# e202-wickervar.net
KiCad netlist of a schematic drawn in EAGLE
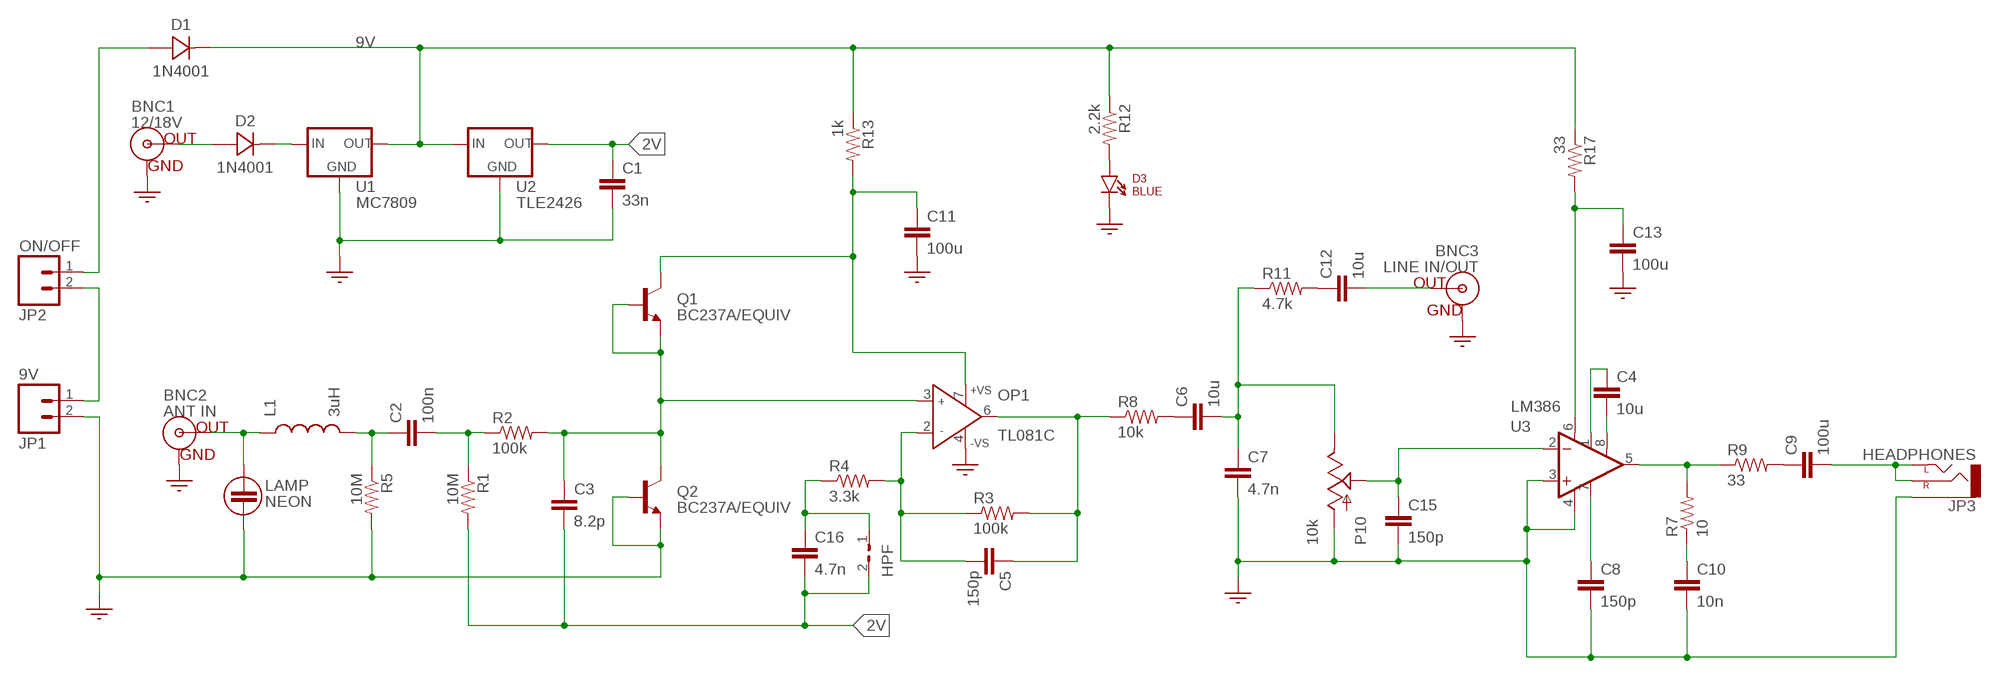
[diagram p0: schematic, sheet 1]

(export (version "E")
  (design (tool "Eeschema 10.0.6"))
  (components
    (comp (ref "BNC1")
      (value "12/18V")
      (footprint "eagle-import:BNC")
      (libsource (lib "eagle-import") (part "BNCPTH"))
    )
    (comp (ref "BNC2")
      (value "ANT IN")
      (footprint "eagle-import:BNC")
      (libsource (lib "eagle-import") (part "BNCPTH"))
    )
    (comp (ref "BNC3")
      (value "LINE IN/OUT")
      (footprint "eagle-import:BNC")
      (libsource (lib "eagle-import") (part "BNCPTH"))
    )
    (comp (ref "C1")
      (value "33n")
      (footprint "eagle-import:CAP-PTH-SMALL-KIT")
      (libsource (lib "eagle-import") (part "CAPKIT"))
    )
    (comp (ref "C2")
      (value "100n")
      (footprint "eagle-import:CAP-PTH-SMALL-KIT")
      (libsource (lib "eagle-import") (part "CAPKIT"))
    )
    (comp (ref "C3")
      (value "8.2p")
      (footprint "eagle-import:CAP-PTH-SMALL-KIT")
      (libsource (lib "eagle-import") (part "CAPKIT"))
    )
    (comp (ref "C4")
      (value "10u")
      (footprint "eagle-import:CAP-PTH-5MM")
      (libsource (lib "eagle-import") (part "SparkFun-Passives_CAPPTH1"))
    )
    (comp (ref "C5")
      (value "150p")
      (footprint "eagle-import:CAP-PTH-SMALL-KIT")
      (libsource (lib "eagle-import") (part "CAPKIT"))
    )
    (comp (ref "C6")
      (value "10u")
      (footprint "eagle-import:CAP-PTH-5MM")
      (libsource (lib "eagle-import") (part "SparkFun-Passives_CAPPTH1"))
    )
    (comp (ref "C7")
      (value "4.7n")
      (footprint "eagle-import:CAP-PTH-5MM")
      (libsource (lib "eagle-import") (part "SparkFun-Passives_CAPPTH1"))
    )
    (comp (ref "C8")
      (value "150p")
      (footprint "eagle-import:CAP-PTH-SMALL-KIT")
      (libsource (lib "eagle-import") (part "CAPKIT"))
    )
    (comp (ref "C9")
      (value "100u")
      (footprint "eagle-import:CAP-PTH-5MM")
      (libsource (lib "eagle-import") (part "SparkFun-Passives_CAPPTH1"))
    )
    (comp (ref "C10")
      (value "10n")
      (footprint "eagle-import:CAP-PTH-SMALL-KIT")
      (libsource (lib "eagle-import") (part "CAPKIT"))
    )
    (comp (ref "C11")
      (value "100u")
      (footprint "eagle-import:CAP-PTH-5MM")
      (libsource (lib "eagle-import") (part "SparkFun-Passives_CAPPTH1"))
    )
    (comp (ref "C12")
      (value "10u")
      (footprint "eagle-import:CAP-PTH-5MM")
      (libsource (lib "eagle-import") (part "SparkFun-Passives_CAPPTH1"))
    )
    (comp (ref "C13")
      (value "100u")
      (footprint "eagle-import:CAP-PTH-5MM")
      (libsource (lib "eagle-import") (part "SparkFun-Passives_CAPPTH1"))
    )
    (comp (ref "C15")
      (value "150p")
      (footprint "eagle-import:CAP-PTH-SMALL-KIT")
      (libsource (lib "eagle-import") (part "CAPKIT"))
    )
    (comp (ref "C16")
      (value "4.7n")
      (footprint "eagle-import:CAP-PTH-SMALL-KIT")
      (libsource (lib "eagle-import") (part "CAPKIT"))
    )
    (comp (ref "D1")
      (value "1N4001")
      (footprint "eagle-import:SMC")
      (libsource (lib "eagle-import") (part "S5BC-13"))
    )
    (comp (ref "D2")
      (value "1N4001")
      (footprint "eagle-import:SMC")
      (libsource (lib "eagle-import") (part "S5BC-13"))
    )
    (comp (ref "D3")
      (value "BLUE")
      (footprint "eagle-import:LTE-302")
      (libsource (lib "eagle-import") (part "LTE-302"))
    )
    (comp (ref "HPF")
      (value "HPF")
      (footprint "eagle-import:1X02_LOCK")
      (libsource (lib "eagle-import") (part "JUMPER-2PTH_LOCK"))
    )
    (comp (ref "JP1")
      (value "9V")
      (footprint "eagle-import:1X02_LOCK")
      (libsource (lib "eagle-import") (part "M02LOCK"))
    )
    (comp (ref "JP2")
      (value "ON/OFF")
      (footprint "eagle-import:1X02_LOCK")
      (libsource (lib "eagle-import") (part "M02LOCK"))
    )
    (comp (ref "JP3")
      (value "HEADPHONES")
      (footprint "eagle-import:STEREOJACK2.5MM_STEREOJACK2.5MM")
      (libsource (lib "eagle-import") (part "AUDIO-JACK2.5MM"))
    )
    (comp (ref "L1")
      (value "3uH")
      (footprint "eagle-import:AXIAL-0.6")
      (libsource (lib "eagle-import") (part "INDUCTORAXIAL-0.6"))
    )
    (comp (ref "LAMP")
      (value "NEON")
      (footprint "eagle-import:ESK337M050AH4AA")
      (libsource (lib "eagle-import") (part "NEONLAMP"))
    )
    (comp (ref "OP1")
      (value "TL081C")
      (footprint "eagle-import:LFCSP8")
      (libsource (lib "eagle-import") (part "AD8597CP"))
    )
    (comp (ref "P10")
      (value "10k")
      (footprint "eagle-import:ALPS_POT")
      (libsource (lib "eagle-import") (part "POT"))
    )
    (comp (ref "Q1")
      (value "BC237A/EQUIV")
      (footprint "eagle-import:TO-92-AMMO")
      (libsource (lib "eagle-import") (part "TRANSISTOR_NPNBC547"))
    )
    (comp (ref "Q2")
      (value "BC237A/EQUIV")
      (footprint "eagle-import:TO-92-AMMO")
      (libsource (lib "eagle-import") (part "TRANSISTOR_NPNBC547"))
    )
    (comp (ref "R1")
      (value "10M")
      (footprint "eagle-import:AXIAL-0.3EZ")
      (libsource (lib "eagle-import") (part "RESISTOREZ"))
    )
    (comp (ref "R2")
      (value "100k")
      (footprint "eagle-import:AXIAL-0.3EZ")
      (libsource (lib "eagle-import") (part "RESISTOREZ"))
    )
    (comp (ref "R3")
      (value "100k")
      (footprint "eagle-import:AXIAL-0.3EZ")
      (libsource (lib "eagle-import") (part "RESISTOREZ"))
    )
    (comp (ref "R4")
      (value "3.3k")
      (footprint "eagle-import:AXIAL-0.3EZ")
      (libsource (lib "eagle-import") (part "RESISTOREZ"))
    )
    (comp (ref "R5")
      (value "10M")
      (footprint "eagle-import:AXIAL-0.3EZ")
      (libsource (lib "eagle-import") (part "RESISTOREZ"))
    )
    (comp (ref "R7")
      (value "10")
      (footprint "eagle-import:AXIAL-0.3EZ")
      (libsource (lib "eagle-import") (part "RESISTOREZ"))
    )
    (comp (ref "R8")
      (value "10k")
      (footprint "eagle-import:AXIAL-0.3EZ")
      (libsource (lib "eagle-import") (part "RESISTOREZ"))
    )
    (comp (ref "R9")
      (value "33")
      (footprint "eagle-import:AXIAL-0.3EZ")
      (libsource (lib "eagle-import") (part "RESISTOREZ"))
    )
    (comp (ref "R11")
      (value "4.7k")
      (footprint "eagle-import:AXIAL-0.3EZ")
      (libsource (lib "eagle-import") (part "RESISTOREZ"))
    )
    (comp (ref "R12")
      (value "2.2k")
      (footprint "eagle-import:AXIAL-0.3EZ")
      (libsource (lib "eagle-import") (part "RESISTOREZ"))
    )
    (comp (ref "R13")
      (value "1k")
      (footprint "eagle-import:AXIAL-0.3EZ")
      (libsource (lib "eagle-import") (part "RESISTOREZ"))
    )
    (comp (ref "R17")
      (value "33")
      (footprint "eagle-import:AXIAL-0.3EZ")
      (libsource (lib "eagle-import") (part "RESISTOREZ"))
    )
    (comp (ref "U1")
      (value "MC7809")
      (footprint "eagle-import:78XXL")
      (libsource (lib "eagle-import") (part "V_REG_LD1117VXX"))
    )
    (comp (ref "U2")
      (value "TLE2426")
      (footprint "eagle-import:78XXL")
      (libsource (lib "eagle-import") (part "V_REG_LD1117VXX"))
    )
    (comp (ref "U3")
      (value "LM386")
      (footprint "eagle-import:DIP08")
      (libsource (lib "eagle-import") (part "LM386"))
    )
  )
  (nets
    (net (code "1") (name "/9V") (class "Default")
      (node (ref "D1") (pin "C") (pinfunction "CATHODE_C") (pintype "passive"))
      (node (ref "R12") (pin "P$1") (pinfunction "1_P$1") (pintype "passive"))
      (node (ref "R13") (pin "P$1") (pinfunction "1_P$1") (pintype "passive"))
      (node (ref "R17") (pin "P$1") (pinfunction "1_P$1") (pintype "passive"))
      (node (ref "U1") (pin "GND") (pinfunction "OUT_GND") (pintype "output"))
      (node (ref "U2") (pin "OUT") (pinfunction "IN_OUT") (pintype "input"))
    )
    (net (code "2") (name "2V") (class "Default")
      (node (ref "C1") (pin "1") (pinfunction "1_1") (pintype "passive"))
      (node (ref "C16") (pin "2") (pinfunction "2_2") (pintype "passive"))
      (node (ref "C3") (pin "2") (pinfunction "2_2") (pintype "passive"))
      (node (ref "HPF") (pin "2") (pinfunction "2_2") (pintype "passive"))
      (node (ref "R1") (pin "P$2") (pinfunction "2_P$2") (pintype "passive"))
      (node (ref "U2") (pin "GND") (pinfunction "OUT_GND") (pintype "output"))
    )
    (net (code "3") (name "GND") (class "Default")
      (node (ref "BNC1") (pin "GND") (pinfunction "GND_GND") (pintype "bidirectional"))
      (node (ref "BNC2") (pin "GND") (pinfunction "GND_GND") (pintype "bidirectional"))
      (node (ref "BNC3") (pin "GND") (pinfunction "GND_GND") (pintype "bidirectional"))
      (node (ref "C1") (pin "2") (pinfunction "2_2") (pintype "passive"))
      (node (ref "C10") (pin "2") (pinfunction "2_2") (pintype "passive"))
      (node (ref "C11") (pin "2") (pinfunction "2_2") (pintype "passive"))
      (node (ref "C13") (pin "2") (pinfunction "2_2") (pintype "passive"))
      (node (ref "C15") (pin "2") (pinfunction "2_2") (pintype "passive"))
      (node (ref "C7") (pin "2") (pinfunction "2_2") (pintype "passive"))
      (node (ref "C8") (pin "2") (pinfunction "2_2") (pintype "passive"))
      (node (ref "D3") (pin "C") (pinfunction "C_C") (pintype "bidirectional"))
      (node (ref "JP1") (pin "2") (pinfunction "2_2") (pintype "passive"))
      (node (ref "JP3") (pin "RING1") (pinfunction "SLEEVE_RING1") (pintype "bidirectional"))
      (node (ref "LAMP") (pin "C") (pinfunction "2_C") (pintype "passive"))
      (node (ref "OP1") (pin "4") (pinfunction "-VS_4") (pintype "input"))
      (node (ref "P10") (pin "P$3") (pinfunction "A_P$3") (pintype "passive"))
      (node (ref "Q2") (pin "2") (pinfunction "B_2") (pintype "passive"))
      (node (ref "Q2") (pin "3") (pinfunction "E_3") (pintype "passive"))
      (node (ref "R5") (pin "P$2") (pinfunction "2_P$2") (pintype "passive"))
      (node (ref "U1") (pin "IN") (pinfunction "GND_IN") (pintype "input"))
      (node (ref "U2") (pin "IN") (pinfunction "GND_IN") (pintype "input"))
      (node (ref "U3") (pin "3") (pinfunction "+IN_3") (pintype "input"))
      (node (ref "U3") (pin "4") (pinfunction "V-_4") (pintype "power_in"))
    )
    (net (code "4") (name "Net-(BNC1-OUT)") (class "Default")
      (node (ref "BNC1") (pin "S") (pinfunction "OUT_S") (pintype "bidirectional"))
      (node (ref "D2") (pin "A") (pinfunction "ANODE_A") (pintype "passive"))
    )
    (net (code "5") (name "Net-(BNC2-OUT)") (class "Default")
      (node (ref "BNC2") (pin "S") (pinfunction "OUT_S") (pintype "bidirectional"))
      (node (ref "L1") (pin "P$1") (pinfunction "1_P$1") (pintype "passive"))
      (node (ref "LAMP") (pin "A") (pinfunction "1_A") (pintype "passive"))
    )
    (net (code "6") (name "Net-(BNC3-OUT)") (class "Default")
      (node (ref "BNC3") (pin "S") (pinfunction "OUT_S") (pintype "bidirectional"))
      (node (ref "C12") (pin "2") (pinfunction "2_2") (pintype "passive"))
    )
    (net (code "7") (name "Net-(C4-Pad1)") (class "Default")
      (node (ref "C4") (pin "1") (pinfunction "1_1") (pintype "passive"))
      (node (ref "U3") (pin "1") (pinfunction "GAIN_1") (pintype "bidirectional"))
    )
    (net (code "8") (name "Net-(C4-Pad2)") (class "Default")
      (node (ref "C4") (pin "2") (pinfunction "2_2") (pintype "passive"))
      (node (ref "U3") (pin "8") (pinfunction "GAIN_8") (pintype "bidirectional"))
    )
    (net (code "9") (name "Net-(D1-ANODE)") (class "Default")
      (node (ref "D1") (pin "A") (pinfunction "ANODE_A") (pintype "passive"))
      (node (ref "JP2") (pin "1") (pinfunction "1_1") (pintype "passive"))
    )
    (net (code "10") (name "Net-(D2-CATHODE)") (class "Default")
      (node (ref "D2") (pin "C") (pinfunction "CATHODE_C") (pintype "passive"))
      (node (ref "U1") (pin "OUT") (pinfunction "IN_OUT") (pintype "input"))
    )
    (net (code "11") (name "Net-(JP1-Pad1)") (class "Default")
      (node (ref "JP1") (pin "1") (pinfunction "1_1") (pintype "passive"))
      (node (ref "JP2") (pin "2") (pinfunction "2_2") (pintype "passive"))
    )
    (net (code "12") (name "Net-(JP3-LEFT)") (class "Default")
      (node (ref "C9") (pin "2") (pinfunction "2_2") (pintype "passive"))
      (node (ref "JP3") (pin "SHIELD") (pinfunction "LEFT_SHIELD") (pintype "bidirectional"))
      (node (ref "JP3") (pin "TIP") (pinfunction "RIGHT_TIP") (pintype "bidirectional"))
    )
    (net (code "13") (name "Net-(L1-2)") (class "Default")
      (node (ref "C2") (pin "1") (pinfunction "1_1") (pintype "passive"))
      (node (ref "L1") (pin "P$2") (pinfunction "2_P$2") (pintype "passive"))
      (node (ref "R5") (pin "P$1") (pinfunction "1_P$1") (pintype "passive"))
    )
    (net (code "14") (name "Net-(OP1-+VS)") (class "Default")
      (node (ref "C11") (pin "1") (pinfunction "1_1") (pintype "passive"))
      (node (ref "OP1") (pin "7") (pinfunction "+VS_7") (pintype "input"))
      (node (ref "Q1") (pin "1") (pinfunction "C_1") (pintype "passive"))
      (node (ref "R13") (pin "P$2") (pinfunction "2_P$2") (pintype "passive"))
    )
    (net (code "15") (name "Net-(OP1-IN+)") (class "Default")
      (node (ref "C3") (pin "1") (pinfunction "1_1") (pintype "passive"))
      (node (ref "OP1") (pin "3") (pinfunction "IN+_3") (pintype "input"))
      (node (ref "Q1") (pin "2") (pinfunction "B_2") (pintype "passive"))
      (node (ref "Q1") (pin "3") (pinfunction "E_3") (pintype "passive"))
      (node (ref "Q2") (pin "1") (pinfunction "C_1") (pintype "passive"))
      (node (ref "R2") (pin "P$2") (pinfunction "2_P$2") (pintype "passive"))
    )
    (net (code "16") (name "Net-(OP1-IN-)") (class "Default")
      (node (ref "C5") (pin "2") (pinfunction "2_2") (pintype "passive"))
      (node (ref "OP1") (pin "2") (pinfunction "IN-_2") (pintype "input"))
      (node (ref "R3") (pin "P$1") (pinfunction "1_P$1") (pintype "passive"))
      (node (ref "R4") (pin "P$2") (pinfunction "2_P$2") (pintype "passive"))
    )
    (net (code "17") (name "Net-(OP1-OUT)") (class "Default")
      (node (ref "C5") (pin "1") (pinfunction "1_1") (pintype "passive"))
      (node (ref "OP1") (pin "6") (pinfunction "OUT_6") (pintype "output"))
      (node (ref "R3") (pin "P$2") (pinfunction "2_P$2") (pintype "passive"))
      (node (ref "R8") (pin "P$1") (pinfunction "1_P$1") (pintype "passive"))
    )
    (net (code "18") (name "Net-(P10-E)") (class "Default")
      (node (ref "C6") (pin "2") (pinfunction "2_2") (pintype "passive"))
      (node (ref "C7") (pin "1") (pinfunction "1_1") (pintype "passive"))
      (node (ref "P10") (pin "P$1") (pinfunction "E_P$1") (pintype "passive"))
      (node (ref "R11") (pin "P$1") (pinfunction "1_P$1") (pintype "passive"))
    )
    (net (code "19") (name "Net-(P10-S)") (class "Default")
      (node (ref "C15") (pin "1") (pinfunction "1_1") (pintype "passive"))
      (node (ref "P10") (pin "P$2") (pinfunction "S_P$2") (pintype "passive"))
      (node (ref "U3") (pin "2") (pinfunction "-IN_2") (pintype "input"))
    )
    (net (code "20") (name "Net-(R1-1)") (class "Default")
      (node (ref "C2") (pin "2") (pinfunction "2_2") (pintype "passive"))
      (node (ref "R1") (pin "P$1") (pinfunction "1_P$1") (pintype "passive"))
      (node (ref "R2") (pin "P$1") (pinfunction "1_P$1") (pintype "passive"))
    )
    (net (code "21") (name "Net-(R4-1)") (class "Default")
      (node (ref "C16") (pin "1") (pinfunction "1_1") (pintype "passive"))
      (node (ref "HPF") (pin "1") (pinfunction "1_1") (pintype "passive"))
      (node (ref "R4") (pin "P$1") (pinfunction "1_P$1") (pintype "passive"))
    )
    (net (code "22") (name "Net-(R7-1)") (class "Default")
      (node (ref "C10") (pin "1") (pinfunction "1_1") (pintype "passive"))
      (node (ref "R7") (pin "P$1") (pinfunction "1_P$1") (pintype "passive"))
    )
    (net (code "23") (name "Net-(R7-2)") (class "Default")
      (node (ref "R7") (pin "P$2") (pinfunction "2_P$2") (pintype "passive"))
      (node (ref "R9") (pin "P$1") (pinfunction "1_P$1") (pintype "passive"))
      (node (ref "U3") (pin "5") (pinfunction "OUT_5") (pintype "output"))
    )
    (net (code "24") (name "Net-(R8-2)") (class "Default")
      (node (ref "C6") (pin "1") (pinfunction "1_1") (pintype "passive"))
      (node (ref "R8") (pin "P$2") (pinfunction "2_P$2") (pintype "passive"))
    )
    (net (code "25") (name "Net-(R9-2)") (class "Default")
      (node (ref "C9") (pin "1") (pinfunction "1_1") (pintype "passive"))
      (node (ref "R9") (pin "P$2") (pinfunction "2_P$2") (pintype "passive"))
    )
    (net (code "26") (name "Net-(R11-2)") (class "Default")
      (node (ref "C12") (pin "1") (pinfunction "1_1") (pintype "passive"))
      (node (ref "R11") (pin "P$2") (pinfunction "2_P$2") (pintype "passive"))
    )
    (net (code "27") (name "Net-(R12-2)") (class "Default")
      (node (ref "D3") (pin "A") (pinfunction "A_A") (pintype "bidirectional"))
      (node (ref "R12") (pin "P$2") (pinfunction "2_P$2") (pintype "passive"))
    )
    (net (code "28") (name "Net-(R17-2)") (class "Default")
      (node (ref "C13") (pin "1") (pinfunction "1_1") (pintype "passive"))
      (node (ref "R17") (pin "P$2") (pinfunction "2_P$2") (pintype "passive"))
      (node (ref "U3") (pin "6") (pinfunction "V+_6") (pintype "power_in"))
    )
    (net (code "29") (name "Net-(U3-BP)") (class "Default")
      (node (ref "C8") (pin "1") (pinfunction "1_1") (pintype "passive"))
      (node (ref "U3") (pin "7") (pinfunction "BP_7") (pintype "bidirectional"))
    )
  )
)
